# BoardV1.net
KiCad netlist of a schematic drawn in EAGLE
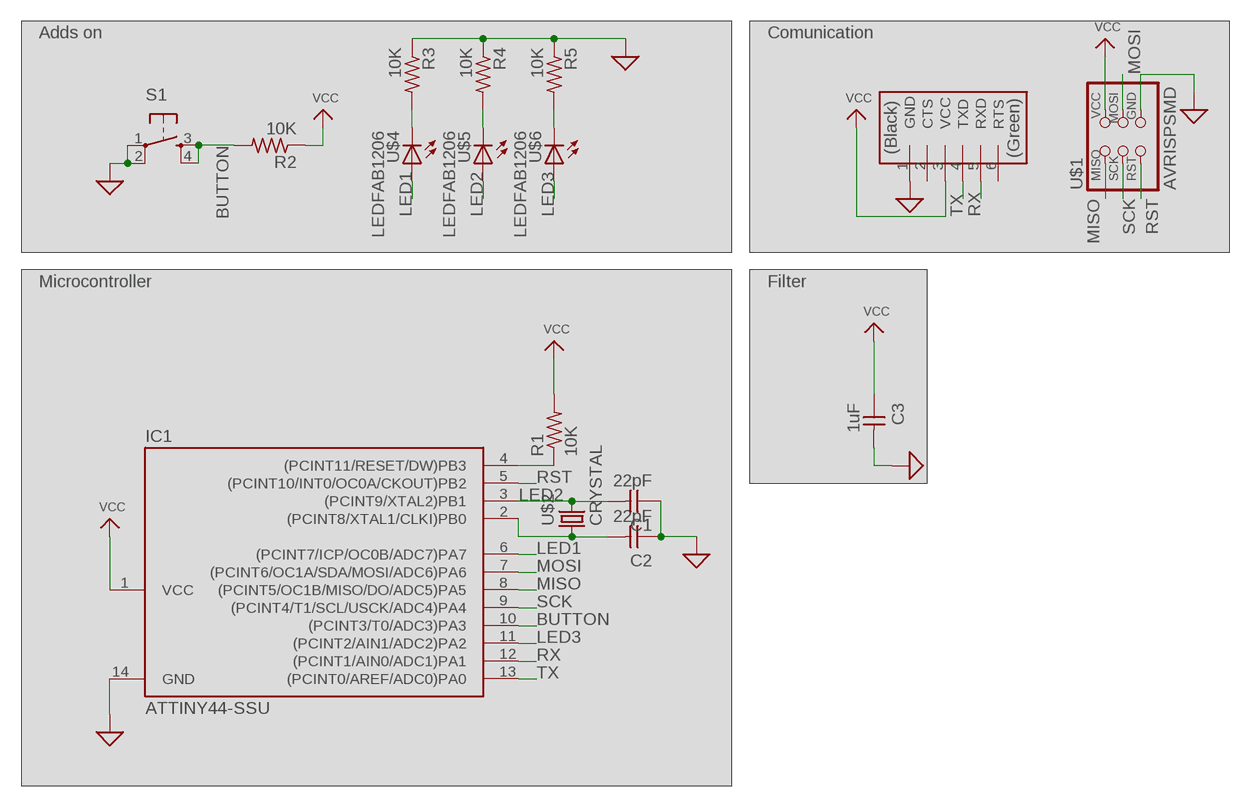
[diagram p0: schematic, sheet 1]

(export (version "E")
  (design (tool "Eeschema 10.0.6"))
  (components
    (comp (ref "C1")
      (value "22pF")
      (footprint "eagle-import:C1206FAB")
      (libsource (lib "eagle-import") (part "CAP-UNPOLARIZEDFAB"))
    )
    (comp (ref "C2")
      (value "22pF")
      (footprint "eagle-import:C1206FAB")
      (libsource (lib "eagle-import") (part "CAP-UNPOLARIZEDFAB"))
    )
    (comp (ref "C3")
      (value "1uF")
      (footprint "eagle-import:C1206FAB")
      (libsource (lib "eagle-import") (part "CAP-UNPOLARIZEDFAB"))
    )
    (comp (ref "IC1")
      (value "ATTINY44-SSU")
      (footprint "eagle-import:SOIC14")
      (libsource (lib "eagle-import") (part "ATTINY44-SSU"))
    )
    (comp (ref "R1")
      (value "10K")
      (footprint "eagle-import:R1206W")
      (libsource (lib "eagle-import") (part "RES-US1206W"))
    )
    (comp (ref "R2")
      (value "10K")
      (footprint "eagle-import:R1206W")
      (libsource (lib "eagle-import") (part "RES-US1206W"))
    )
    (comp (ref "R3")
      (value "10K")
      (footprint "eagle-import:R1206W")
      (libsource (lib "eagle-import") (part "RES-US1206W"))
    )
    (comp (ref "R4")
      (value "10K")
      (footprint "eagle-import:R1206W")
      (libsource (lib "eagle-import") (part "RES-US1206W"))
    )
    (comp (ref "R5")
      (value "10K")
      (footprint "eagle-import:R1206W")
      (libsource (lib "eagle-import") (part "RES-US1206W"))
    )
    (comp (ref "S1")
      (value "6MM_SWITCH6MM_SWITCH")
      (footprint "eagle-import:6MM_SWITCH")
      (fields (field (name "SPICEPREFIX") "S"))
      (libsource (lib "eagle-import") (part "6MM_SWITCH6MM_SWITCH"))
    )
    (comp (ref "U$1")
      (value "AVRISPSMD")
      (footprint "eagle-import:2X03SMD")
      (libsource (lib "eagle-import") (part "AVRISPSMD"))
    )
    (comp (ref "U$2")
      (value "CRYSTAL")
      (footprint "eagle-import:2-SMD-5X3MM")
      (libsource (lib "eagle-import") (part "CRYSTAL"))
    )
    (comp (ref "U$3")
      (value "FTDI-SMD-HEADER")
      (footprint "eagle-import:1X06SMD")
      (libsource (lib "eagle-import") (part "FTDI-SMD-HEADER"))
    )
    (comp (ref "U$4")
      (value "LEDFAB1206")
      (footprint "eagle-import:LED1206FAB")
      (libsource (lib "eagle-import") (part "LEDFAB1206"))
    )
    (comp (ref "U$5")
      (value "LEDFAB1206")
      (footprint "eagle-import:LED1206FAB")
      (libsource (lib "eagle-import") (part "LEDFAB1206"))
    )
    (comp (ref "U$6")
      (value "LEDFAB1206")
      (footprint "eagle-import:LED1206FAB")
      (libsource (lib "eagle-import") (part "LEDFAB1206"))
    )
  )
  (nets
    (net (code "1") (name "/BUTTON") (class "Default")
      (node (ref "IC1") (pin "10") (pinfunction "(PCINT3/T0/ADC3)PA3_10") (pintype "bidirectional"))
      (node (ref "R2") (pin "2") (pinfunction "2_2") (pintype "passive"))
      (node (ref "S1") (pin "3") (pinfunction "S_3") (pintype "passive"))
      (node (ref "S1") (pin "4") (pinfunction "S1_4") (pintype "passive"))
    )
    (net (code "2") (name "/LED1") (class "Default")
      (node (ref "IC1") (pin "6") (pinfunction "(PCINT7/ICP/OC0B/ADC7)PA7_6") (pintype "bidirectional"))
      (node (ref "U$4") (pin "1") (pinfunction "A_1") (pintype "passive"))
    )
    (net (code "3") (name "/LED2") (class "Default")
      (node (ref "IC1") (pin "5") (pinfunction "(PCINT10/INT0/OC0A/CKOUT)PB2_5") (pintype "bidirectional"))
      (node (ref "U$5") (pin "1") (pinfunction "A_1") (pintype "passive"))
    )
    (net (code "4") (name "/LED3") (class "Default")
      (node (ref "IC1") (pin "11") (pinfunction "(PCINT2/AIN1/ADC2)PA2_11") (pintype "bidirectional"))
      (node (ref "U$6") (pin "1") (pinfunction "A_1") (pintype "passive"))
    )
    (net (code "5") (name "/MISO") (class "Default")
      (node (ref "IC1") (pin "8") (pinfunction "(PCINT5/OC1B/MISO/DO/ADC5)PA5_8") (pintype "bidirectional"))
      (node (ref "U$1") (pin "1") (pinfunction "MISO_1") (pintype "passive"))
    )
    (net (code "6") (name "/MOSI") (class "Default")
      (node (ref "IC1") (pin "7") (pinfunction "(PCINT6/OC1A/SDA/MOSI/ADC6)PA6_7") (pintype "bidirectional"))
      (node (ref "U$1") (pin "4") (pinfunction "MOSI_4") (pintype "passive"))
    )
    (net (code "7") (name "/RST") (class "Default")
      (node (ref "IC1") (pin "4") (pinfunction "(PCINT11/RESET/DW)PB3_4") (pintype "bidirectional"))
      (node (ref "R1") (pin "1") (pinfunction "1_1") (pintype "passive"))
      (node (ref "U$1") (pin "5") (pinfunction "RST_5") (pintype "passive"))
    )
    (net (code "8") (name "/RX") (class "Default")
      (node (ref "IC1") (pin "12") (pinfunction "(PCINT1/AIN0/ADC1)PA1_12") (pintype "bidirectional"))
      (node (ref "U$3") (pin "5") (pinfunction "RXD_5") (pintype "bidirectional"))
    )
    (net (code "9") (name "/SCK") (class "Default")
      (node (ref "IC1") (pin "9") (pinfunction "(PCINT4/T1/SCL/USCK/ADC4)PA4_9") (pintype "bidirectional"))
      (node (ref "U$1") (pin "3") (pinfunction "SCK_3") (pintype "passive"))
    )
    (net (code "10") (name "/TX") (class "Default")
      (node (ref "IC1") (pin "13") (pinfunction "(PCINT0/AREF/ADC0)PA0_13") (pintype "bidirectional"))
      (node (ref "U$3") (pin "4") (pinfunction "TXD_4") (pintype "bidirectional"))
    )
    (net (code "11") (name "Net-(IC1-(PCINT8{slash}XTAL1{slash}CLKI)PB0)") (class "Default")
      (node (ref "C2") (pin "2") (pinfunction "2_2") (pintype "passive"))
      (node (ref "IC1") (pin "2") (pinfunction "(PCINT8/XTAL1/CLKI)PB0_2") (pintype "bidirectional"))
      (node (ref "U$2") (pin "P$1") (pinfunction "1_P$1") (pintype "passive"))
    )
    (net (code "12") (name "Net-(IC1-(PCINT9{slash}XTAL2)PB1)") (class "Default")
      (node (ref "C1") (pin "2") (pinfunction "2_2") (pintype "passive"))
      (node (ref "IC1") (pin "3") (pinfunction "(PCINT9/XTAL2)PB1_3") (pintype "bidirectional"))
      (node (ref "U$2") (pin "P$2") (pinfunction "2_P$2") (pintype "passive"))
    )
    (net (code "13") (name "Net-(U$4-C)") (class "Default")
      (node (ref "R3") (pin "2") (pinfunction "2_2") (pintype "passive"))
      (node (ref "U$4") (pin "2") (pinfunction "C_2") (pintype "passive"))
    )
    (net (code "14") (name "Net-(U$5-C)") (class "Default")
      (node (ref "R4") (pin "2") (pinfunction "2_2") (pintype "passive"))
      (node (ref "U$5") (pin "2") (pinfunction "C_2") (pintype "passive"))
    )
    (net (code "15") (name "Net-(U$6-C)") (class "Default")
      (node (ref "R5") (pin "2") (pinfunction "2_2") (pintype "passive"))
      (node (ref "U$6") (pin "2") (pinfunction "C_2") (pintype "passive"))
    )
    (net (code "16") (name "SUP") (class "Default")
      (node (ref "C1") (pin "1") (pinfunction "1_1") (pintype "passive"))
      (node (ref "C2") (pin "1") (pinfunction "1_1") (pintype "passive"))
      (node (ref "C3") (pin "2") (pinfunction "2_2") (pintype "passive"))
      (node (ref "IC1") (pin "14") (pinfunction "GND_14") (pintype "power_in"))
      (node (ref "R3") (pin "1") (pinfunction "1_1") (pintype "passive"))
      (node (ref "R4") (pin "1") (pinfunction "1_1") (pintype "passive"))
      (node (ref "R5") (pin "1") (pinfunction "1_1") (pintype "passive"))
      (node (ref "S1") (pin "1") (pinfunction "P_1") (pintype "passive"))
      (node (ref "S1") (pin "2") (pinfunction "P1_2") (pintype "passive"))
      (node (ref "U$1") (pin "6") (pinfunction "GND_6") (pintype "passive"))
      (node (ref "U$3") (pin "1") (pinfunction "GND_1") (pintype "bidirectional"))
    )
    (net (code "17") (name "VCC") (class "Default")
      (node (ref "C3") (pin "1") (pinfunction "1_1") (pintype "passive"))
      (node (ref "IC1") (pin "1") (pinfunction "VCC_1") (pintype "power_in"))
      (node (ref "R1") (pin "2") (pinfunction "2_2") (pintype "passive"))
      (node (ref "R2") (pin "1") (pinfunction "1_1") (pintype "passive"))
      (node (ref "U$1") (pin "2") (pinfunction "VCC_2") (pintype "passive"))
      (node (ref "U$3") (pin "3") (pinfunction "VCC_3") (pintype "bidirectional"))
    )
    (net (code "18") (name "unconnected-(U$3-CTS-Pad2)") (class "Default")
      (node (ref "U$3") (pin "2") (pinfunction "CTS_2") (pintype "bidirectional"))
    )
    (net (code "19") (name "unconnected-(U$3-RTS-Pad6)") (class "Default")
      (node (ref "U$3") (pin "6") (pinfunction "RTS_6") (pintype "bidirectional"))
    )
  )
)
